# daq_pitot_tube_breakout.net
KiCad netlist of a schematic drawn in EAGLE
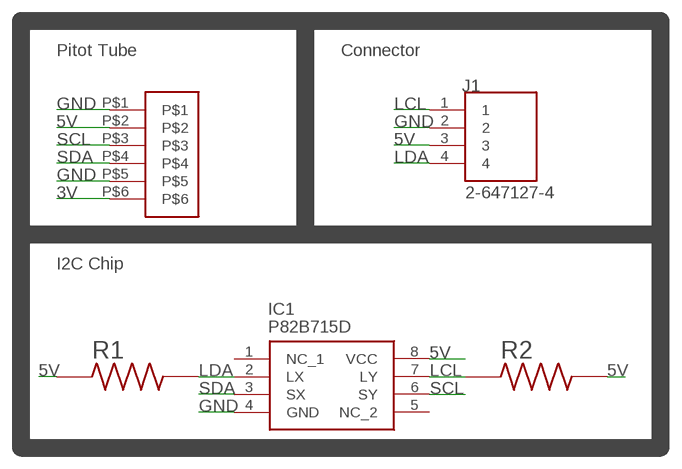
[diagram p0: schematic, sheet 1]

(export (version "E")
  (design (tool "Eeschema 10.0.6"))
  (components
    (comp (ref "IC1")
      (value "P82B715D")
      (footprint "eagle-import:SOIC127P600X175-8N")
      (fields (field (name "MOUSER_PART_NUMBER") "595-P82B715D"))
      (libsource (lib "eagle-import") (part "P82B715D"))
    )
    (comp (ref "J1")
      (value "2-647127-4")
      (footprint "eagle-import:TE_2-647127-4")
      (fields (field (name "DIGI-KEY_PART_NUMBER") "A122823-ND") (field (name "MF") "TE Connectivity"))
      (libsource (lib "eagle-import") (part "2-647127-4"))
    )
    (comp (ref "R1")
      (value "RMCF1206JT10K0")
      (footprint "eagle-import:RESC3216X70N")
      (fields
        (field (name "DIGI-KEY_PART_NUMBER") "RMCF1206JT10K0CT-ND")
        (field (name "MF") "Stackpole Electronics Inc")
      )
      (libsource (lib "eagle-import") (part "RMCF1206JT10K0"))
    )
    (comp (ref "R2")
      (value "RMCF1206JT10K0")
      (footprint "eagle-import:RESC3216X70N")
      (fields
        (field (name "DIGI-KEY_PART_NUMBER") "RMCF1206JT10K0CT-ND")
        (field (name "MF") "Stackpole Electronics Inc")
      )
      (libsource (lib "eagle-import") (part "RMCF1206JT10K0"))
    )
    (comp (ref "U$1")
      (value "ASPD-4525")
      (footprint "eagle-import:ASPD-4525")
      (libsource (lib "eagle-import") (part "ASPD-4525"))
    )
  )
  (nets
    (net (code "1") (name "/3V") (class "Default")
      (node (ref "U$1") (pin "P$6") (pinfunction "P$6_P$6") (pintype "bidirectional"))
    )
    (net (code "2") (name "/5V") (class "Default")
      (node (ref "IC1") (pin "8") (pinfunction "VCC_8") (pintype "bidirectional"))
      (node (ref "J1") (pin "3") (pinfunction "3_3") (pintype "passive"))
      (node (ref "R1") (pin "1") (pinfunction "1_1") (pintype "passive"))
      (node (ref "R2") (pin "2") (pinfunction "2_2") (pintype "passive"))
      (node (ref "U$1") (pin "P$2") (pinfunction "P$2_P$2") (pintype "bidirectional"))
    )
    (net (code "3") (name "/GND") (class "Default")
      (node (ref "IC1") (pin "4") (pinfunction "GND_4") (pintype "bidirectional"))
      (node (ref "J1") (pin "2") (pinfunction "2_2") (pintype "passive"))
      (node (ref "U$1") (pin "P$1") (pinfunction "P$1_P$1") (pintype "bidirectional"))
      (node (ref "U$1") (pin "P$5") (pinfunction "P$5_P$5") (pintype "bidirectional"))
    )
    (net (code "4") (name "/LCL") (class "Default")
      (node (ref "IC1") (pin "7") (pinfunction "LY_7") (pintype "bidirectional"))
      (node (ref "J1") (pin "1") (pinfunction "1_1") (pintype "passive"))
      (node (ref "R2") (pin "1") (pinfunction "1_1") (pintype "passive"))
    )
    (net (code "5") (name "/LDA") (class "Default")
      (node (ref "IC1") (pin "2") (pinfunction "LX_2") (pintype "bidirectional"))
      (node (ref "J1") (pin "4") (pinfunction "4_4") (pintype "passive"))
      (node (ref "R1") (pin "2") (pinfunction "2_2") (pintype "passive"))
    )
    (net (code "6") (name "/SCL") (class "Default")
      (node (ref "IC1") (pin "6") (pinfunction "SY_6") (pintype "bidirectional"))
      (node (ref "U$1") (pin "P$3") (pinfunction "P$3_P$3") (pintype "bidirectional"))
    )
    (net (code "7") (name "/SDA") (class "Default")
      (node (ref "IC1") (pin "3") (pinfunction "SX_3") (pintype "bidirectional"))
      (node (ref "U$1") (pin "P$4") (pinfunction "P$4_P$4") (pintype "bidirectional"))
    )
    (net (code "8") (name "unconnected-(IC1-NC_1-Pad1)") (class "Default")
      (node (ref "IC1") (pin "1") (pinfunction "NC_1_1") (pintype "bidirectional"))
    )
    (net (code "9") (name "unconnected-(IC1-NC_2-Pad5)") (class "Default")
      (node (ref "IC1") (pin "5") (pinfunction "NC_2_5") (pintype "bidirectional"))
    )
  )
)
